# powersupplyboardinprogress.net
KiCad netlist of a schematic drawn in EAGLE
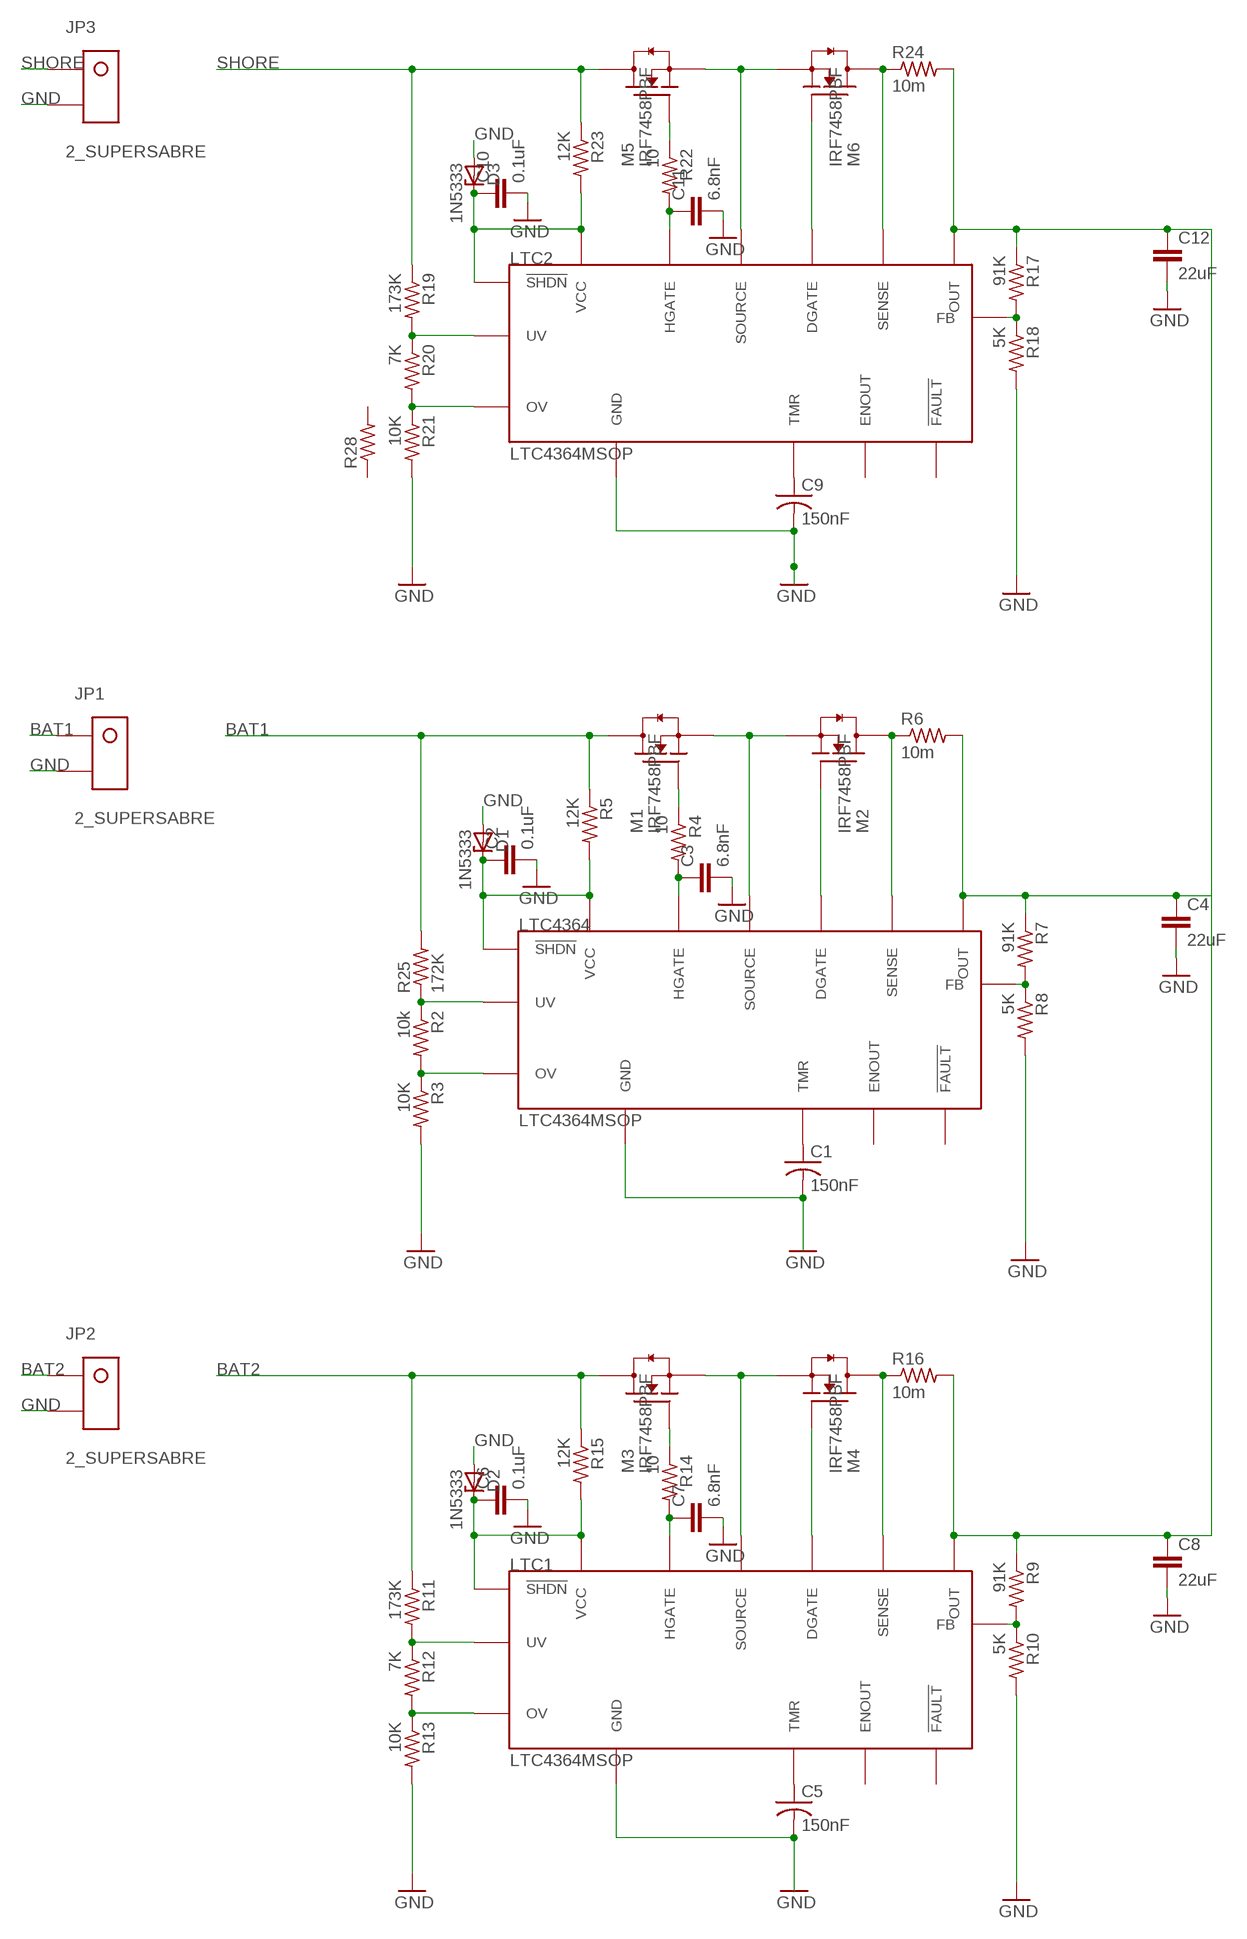
[diagram p0: schematic, sheet 1]

(export (version "E")
  (design (tool "Eeschema 10.0.6"))
  (components
    (comp (ref "C1")
      (value "150nF")
      (footprint "eagle-import:C0805")
      (fields (field (name "SPICEPREFIX") "C"))
      (libsource (lib "eagle-import") (part "C-USC0805"))
    )
    (comp (ref "C2")
      (value "0.1uF")
      (footprint "eagle-import:C0805")
      (libsource (lib "eagle-import") (part "C-EUC0805"))
    )
    (comp (ref "C3")
      (value "6.8nF")
      (footprint "eagle-import:C0805")
      (libsource (lib "eagle-import") (part "C-EUC0805"))
    )
    (comp (ref "C4")
      (value "22uF")
      (footprint "eagle-import:C0805")
      (libsource (lib "eagle-import") (part "C-EUC0805"))
    )
    (comp (ref "C5")
      (value "150nF")
      (footprint "eagle-import:C0805")
      (fields (field (name "SPICEPREFIX") "C"))
      (libsource (lib "eagle-import") (part "C-USC0805"))
    )
    (comp (ref "C6")
      (value "0.1uF")
      (footprint "eagle-import:C0805")
      (libsource (lib "eagle-import") (part "C-EUC0805"))
    )
    (comp (ref "C7")
      (value "6.8nF")
      (footprint "eagle-import:C0805")
      (libsource (lib "eagle-import") (part "C-EUC0805"))
    )
    (comp (ref "C8")
      (value "22uF")
      (footprint "eagle-import:C0805")
      (libsource (lib "eagle-import") (part "C-EUC0805"))
    )
    (comp (ref "C9")
      (value "150nF")
      (footprint "eagle-import:C0805")
      (fields (field (name "SPICEPREFIX") "C"))
      (libsource (lib "eagle-import") (part "C-USC0805"))
    )
    (comp (ref "C10")
      (value "0.1uF")
      (footprint "eagle-import:C0805")
      (libsource (lib "eagle-import") (part "C-EUC0805"))
    )
    (comp (ref "C11")
      (value "6.8nF")
      (footprint "eagle-import:C0805")
      (libsource (lib "eagle-import") (part "C-EUC0805"))
    )
    (comp (ref "C12")
      (value "22uF")
      (footprint "eagle-import:C0805")
      (libsource (lib "eagle-import") (part "C-EUC0805"))
    )
    (comp (ref "D1")
      (value "1N5333")
      (footprint "eagle-import:C1702-15")
      (libsource (lib "eagle-import") (part "1N5333"))
    )
    (comp (ref "D2")
      (value "1N5333")
      (footprint "eagle-import:C1702-15")
      (libsource (lib "eagle-import") (part "1N5333"))
    )
    (comp (ref "D3")
      (value "1N5333")
      (footprint "eagle-import:C1702-15")
      (libsource (lib "eagle-import") (part "1N5333"))
    )
    (comp (ref "JP1")
      (value "2_SUPERSABRE")
      (footprint "eagle-import:SUPERSABRE_2CIRCUIT")
      (libsource (lib "eagle-import") (part "2_SUPERSABRE"))
    )
    (comp (ref "JP2")
      (value "2_SUPERSABRE")
      (footprint "eagle-import:SUPERSABRE_2CIRCUIT")
      (libsource (lib "eagle-import") (part "2_SUPERSABRE"))
    )
    (comp (ref "JP3")
      (value "2_SUPERSABRE")
      (footprint "eagle-import:SUPERSABRE_2CIRCUIT")
      (libsource (lib "eagle-import") (part "2_SUPERSABRE"))
    )
    (comp (ref "LTC1")
      (value "LTC4364MSOP")
      (footprint "eagle-import:MSOP16")
      (fields (field (name "SPICEPREFIX") "X"))
      (libsource (lib "eagle-import") (part "LTC4364MSOP"))
    )
    (comp (ref "LTC2")
      (value "LTC4364MSOP")
      (footprint "eagle-import:MSOP16")
      (fields (field (name "SPICEPREFIX") "X"))
      (libsource (lib "eagle-import") (part "LTC4364MSOP"))
    )
    (comp (ref "LTC4364")
      (value "LTC4364MSOP")
      (footprint "eagle-import:MSOP16")
      (fields (field (name "SPICEPREFIX") "X"))
      (libsource (lib "eagle-import") (part "LTC4364MSOP"))
    )
    (comp (ref "M1")
      (value "IRF7458PBF")
      (footprint "eagle-import:SOIC8")
      (fields (field (name "SPICEPREFIX") "M"))
      (libsource (lib "eagle-import") (part "IRF7458PBF"))
    )
    (comp (ref "M2")
      (value "IRF7458PBF")
      (footprint "eagle-import:SOIC8")
      (fields (field (name "SPICEPREFIX") "M"))
      (libsource (lib "eagle-import") (part "IRF7458PBF"))
    )
    (comp (ref "M3")
      (value "IRF7458PBF")
      (footprint "eagle-import:SOIC8")
      (fields (field (name "SPICEPREFIX") "M"))
      (libsource (lib "eagle-import") (part "IRF7458PBF"))
    )
    (comp (ref "M4")
      (value "IRF7458PBF")
      (footprint "eagle-import:SOIC8")
      (fields (field (name "SPICEPREFIX") "M"))
      (libsource (lib "eagle-import") (part "IRF7458PBF"))
    )
    (comp (ref "M5")
      (value "IRF7458PBF")
      (footprint "eagle-import:SOIC8")
      (fields (field (name "SPICEPREFIX") "M"))
      (libsource (lib "eagle-import") (part "IRF7458PBF"))
    )
    (comp (ref "M6")
      (value "IRF7458PBF")
      (footprint "eagle-import:SOIC8")
      (fields (field (name "SPICEPREFIX") "M"))
      (libsource (lib "eagle-import") (part "IRF7458PBF"))
    )
    (comp (ref "R2")
      (value "10k")
      (footprint "eagle-import:R0805")
      (libsource (lib "eagle-import") (part "R-US_R0805"))
    )
    (comp (ref "R3")
      (value "10K")
      (footprint "eagle-import:R0805")
      (libsource (lib "eagle-import") (part "R-US_R0805"))
    )
    (comp (ref "R4")
      (value "10")
      (footprint "eagle-import:R0805")
      (libsource (lib "eagle-import") (part "R-US_R0805"))
    )
    (comp (ref "R5")
      (value "12K")
      (footprint "eagle-import:R0805")
      (libsource (lib "eagle-import") (part "R-US_R0805"))
    )
    (comp (ref "R6")
      (value "10m")
      (footprint "eagle-import:R0805")
      (libsource (lib "eagle-import") (part "R-US_R0805"))
    )
    (comp (ref "R7")
      (value "91K")
      (footprint "eagle-import:R0805")
      (libsource (lib "eagle-import") (part "R-US_R0805"))
    )
    (comp (ref "R8")
      (value "5K")
      (footprint "eagle-import:R0805")
      (libsource (lib "eagle-import") (part "R-US_R0805"))
    )
    (comp (ref "R9")
      (value "91K")
      (footprint "eagle-import:R0805")
      (libsource (lib "eagle-import") (part "R-US_R0805"))
    )
    (comp (ref "R10")
      (value "5K")
      (footprint "eagle-import:R0805")
      (libsource (lib "eagle-import") (part "R-US_R0805"))
    )
    (comp (ref "R11")
      (value "173K")
      (footprint "eagle-import:R0805")
      (libsource (lib "eagle-import") (part "R-US_R0805"))
    )
    (comp (ref "R12")
      (value "7K")
      (footprint "eagle-import:R0805")
      (libsource (lib "eagle-import") (part "R-US_R0805"))
    )
    (comp (ref "R13")
      (value "10K")
      (footprint "eagle-import:R0805")
      (libsource (lib "eagle-import") (part "R-US_R0805"))
    )
    (comp (ref "R14")
      (value "10")
      (footprint "eagle-import:R0805")
      (libsource (lib "eagle-import") (part "R-US_R0805"))
    )
    (comp (ref "R15")
      (value "12K")
      (footprint "eagle-import:R0805")
      (libsource (lib "eagle-import") (part "R-US_R0805"))
    )
    (comp (ref "R16")
      (value "10m")
      (footprint "eagle-import:R0805")
      (libsource (lib "eagle-import") (part "R-US_R0805"))
    )
    (comp (ref "R17")
      (value "91K")
      (footprint "eagle-import:R0805")
      (libsource (lib "eagle-import") (part "R-US_R0805"))
    )
    (comp (ref "R18")
      (value "5K")
      (footprint "eagle-import:R0805")
      (libsource (lib "eagle-import") (part "R-US_R0805"))
    )
    (comp (ref "R19")
      (value "173K")
      (footprint "eagle-import:R0805")
      (libsource (lib "eagle-import") (part "R-US_R0805"))
    )
    (comp (ref "R20")
      (value "7K")
      (footprint "eagle-import:R0805")
      (libsource (lib "eagle-import") (part "R-US_R0805"))
    )
    (comp (ref "R21")
      (value "10K")
      (footprint "eagle-import:R0805")
      (libsource (lib "eagle-import") (part "R-US_R0805"))
    )
    (comp (ref "R22")
      (value "10")
      (footprint "eagle-import:R0805")
      (libsource (lib "eagle-import") (part "R-US_R0805"))
    )
    (comp (ref "R23")
      (value "12K")
      (footprint "eagle-import:R0805")
      (libsource (lib "eagle-import") (part "R-US_R0805"))
    )
    (comp (ref "R24")
      (value "10m")
      (footprint "eagle-import:R0805")
      (libsource (lib "eagle-import") (part "R-US_R0805"))
    )
    (comp (ref "R25")
      (value "172K")
      (footprint "eagle-import:R0603")
      (libsource (lib "eagle-import") (part "R-US_R0603"))
    )
    (comp (ref "R28")
      (value "R-US_R0603")
      (footprint "eagle-import:R0603")
      (libsource (lib "eagle-import") (part "R-US_R0603"))
    )
  )
  (nets
    (net (code "1") (name "/BAT1") (class "Default")
      (node (ref "JP1") (pin "P$1") (pinfunction "P$1_P$1") (pintype "bidirectional"))
      (node (ref "M1") (pin "D1") (pinfunction "D_D1") (pintype "bidirectional"))
      (node (ref "M1") (pin "D2") (pinfunction "D_D2") (pintype "bidirectional"))
      (node (ref "M1") (pin "D3") (pinfunction "D_D3") (pintype "bidirectional"))
      (node (ref "M1") (pin "D4") (pinfunction "D_D4") (pintype "bidirectional"))
      (node (ref "R25") (pin "2") (pinfunction "2_2") (pintype "passive"))
      (node (ref "R5") (pin "1") (pinfunction "1_1") (pintype "passive"))
    )
    (net (code "2") (name "/BAT2") (class "Default")
      (node (ref "JP2") (pin "P$1") (pinfunction "P$1_P$1") (pintype "bidirectional"))
      (node (ref "M3") (pin "D1") (pinfunction "D_D1") (pintype "bidirectional"))
      (node (ref "M3") (pin "D2") (pinfunction "D_D2") (pintype "bidirectional"))
      (node (ref "M3") (pin "D3") (pinfunction "D_D3") (pintype "bidirectional"))
      (node (ref "M3") (pin "D4") (pinfunction "D_D4") (pintype "bidirectional"))
      (node (ref "R11") (pin "1") (pinfunction "1_1") (pintype "passive"))
      (node (ref "R15") (pin "1") (pinfunction "1_1") (pintype "passive"))
    )
    (net (code "3") (name "/SHORE") (class "Default")
      (node (ref "JP3") (pin "P$1") (pinfunction "P$1_P$1") (pintype "bidirectional"))
      (node (ref "M5") (pin "D1") (pinfunction "D_D1") (pintype "bidirectional"))
      (node (ref "M5") (pin "D2") (pinfunction "D_D2") (pintype "bidirectional"))
      (node (ref "M5") (pin "D3") (pinfunction "D_D3") (pintype "bidirectional"))
      (node (ref "M5") (pin "D4") (pinfunction "D_D4") (pintype "bidirectional"))
      (node (ref "R19") (pin "1") (pinfunction "1_1") (pintype "passive"))
      (node (ref "R23") (pin "1") (pinfunction "1_1") (pintype "passive"))
    )
    (net (code "4") (name "GND") (class "Default")
      (node (ref "C1") (pin "2") (pinfunction "2_2") (pintype "passive"))
      (node (ref "C10") (pin "2") (pinfunction "2_2") (pintype "passive"))
      (node (ref "C11") (pin "2") (pinfunction "2_2") (pintype "passive"))
      (node (ref "C12") (pin "2") (pinfunction "2_2") (pintype "passive"))
      (node (ref "C2") (pin "2") (pinfunction "2_2") (pintype "passive"))
      (node (ref "C3") (pin "2") (pinfunction "2_2") (pintype "passive"))
      (node (ref "C4") (pin "2") (pinfunction "2_2") (pintype "passive"))
      (node (ref "C5") (pin "2") (pinfunction "2_2") (pintype "passive"))
      (node (ref "C6") (pin "2") (pinfunction "2_2") (pintype "passive"))
      (node (ref "C7") (pin "2") (pinfunction "2_2") (pintype "passive"))
      (node (ref "C8") (pin "2") (pinfunction "2_2") (pintype "passive"))
      (node (ref "C9") (pin "2") (pinfunction "2_2") (pintype "passive"))
      (node (ref "D1") (pin "A") (pinfunction "A_A") (pintype "passive"))
      (node (ref "D2") (pin "A") (pinfunction "A_A") (pintype "passive"))
      (node (ref "D3") (pin "A") (pinfunction "A_A") (pintype "passive"))
      (node (ref "JP1") (pin "P$2") (pinfunction "P$2_P$2") (pintype "bidirectional"))
      (node (ref "JP2") (pin "P$2") (pinfunction "P$2_P$2") (pintype "bidirectional"))
      (node (ref "JP3") (pin "P$2") (pinfunction "P$2_P$2") (pintype "bidirectional"))
      (node (ref "LTC1") (pin "GND") (pinfunction "GND_GND") (pintype "bidirectional"))
      (node (ref "LTC2") (pin "GND") (pinfunction "GND_GND") (pintype "bidirectional"))
      (node (ref "LTC4364") (pin "GND") (pinfunction "GND_GND") (pintype "bidirectional"))
      (node (ref "R10") (pin "2") (pinfunction "2_2") (pintype "passive"))
      (node (ref "R13") (pin "2") (pinfunction "2_2") (pintype "passive"))
      (node (ref "R18") (pin "2") (pinfunction "2_2") (pintype "passive"))
      (node (ref "R21") (pin "2") (pinfunction "2_2") (pintype "passive"))
      (node (ref "R3") (pin "2") (pinfunction "2_2") (pintype "passive"))
      (node (ref "R8") (pin "2") (pinfunction "2_2") (pintype "passive"))
    )
    (net (code "5") (name "Net-(C1-Pad1)") (class "Default")
      (node (ref "C1") (pin "1") (pinfunction "1_1") (pintype "passive"))
      (node (ref "LTC4364") (pin "TMR") (pinfunction "TMR_TMR") (pintype "bidirectional"))
    )
    (net (code "6") (name "Net-(C3-Pad1)") (class "Default")
      (node (ref "C3") (pin "1") (pinfunction "1_1") (pintype "passive"))
      (node (ref "LTC4364") (pin "HGATE") (pinfunction "HGATE_HGATE") (pintype "bidirectional"))
      (node (ref "R4") (pin "2") (pinfunction "2_2") (pintype "passive"))
    )
    (net (code "7") (name "Net-(C5-Pad1)") (class "Default")
      (node (ref "C5") (pin "1") (pinfunction "1_1") (pintype "passive"))
      (node (ref "LTC1") (pin "TMR") (pinfunction "TMR_TMR") (pintype "bidirectional"))
    )
    (net (code "8") (name "Net-(C7-Pad1)") (class "Default")
      (node (ref "C7") (pin "1") (pinfunction "1_1") (pintype "passive"))
      (node (ref "LTC1") (pin "HGATE") (pinfunction "HGATE_HGATE") (pintype "bidirectional"))
      (node (ref "R14") (pin "2") (pinfunction "2_2") (pintype "passive"))
    )
    (net (code "9") (name "Net-(C9-Pad1)") (class "Default")
      (node (ref "C9") (pin "1") (pinfunction "1_1") (pintype "passive"))
      (node (ref "LTC2") (pin "TMR") (pinfunction "TMR_TMR") (pintype "bidirectional"))
    )
    (net (code "10") (name "Net-(C11-Pad1)") (class "Default")
      (node (ref "C11") (pin "1") (pinfunction "1_1") (pintype "passive"))
      (node (ref "LTC2") (pin "HGATE") (pinfunction "HGATE_HGATE") (pintype "bidirectional"))
      (node (ref "R22") (pin "2") (pinfunction "2_2") (pintype "passive"))
    )
    (net (code "11") (name "Net-(C12-Pad1)") (class "Default")
      (node (ref "C12") (pin "1") (pinfunction "1_1") (pintype "passive"))
      (node (ref "C4") (pin "1") (pinfunction "1_1") (pintype "passive"))
      (node (ref "C8") (pin "1") (pinfunction "1_1") (pintype "passive"))
      (node (ref "LTC1") (pin "OUT") (pinfunction "OUT_OUT") (pintype "bidirectional"))
      (node (ref "LTC2") (pin "OUT") (pinfunction "OUT_OUT") (pintype "bidirectional"))
      (node (ref "LTC4364") (pin "OUT") (pinfunction "OUT_OUT") (pintype "bidirectional"))
      (node (ref "R16") (pin "2") (pinfunction "2_2") (pintype "passive"))
      (node (ref "R17") (pin "1") (pinfunction "1_1") (pintype "passive"))
      (node (ref "R24") (pin "2") (pinfunction "2_2") (pintype "passive"))
      (node (ref "R6") (pin "2") (pinfunction "2_2") (pintype "passive"))
      (node (ref "R7") (pin "1") (pinfunction "1_1") (pintype "passive"))
      (node (ref "R9") (pin "1") (pinfunction "1_1") (pintype "passive"))
    )
    (net (code "12") (name "Net-(LTC1-PadFB)") (class "Default")
      (node (ref "LTC1") (pin "FB") (pinfunction "FB_FB") (pintype "bidirectional"))
      (node (ref "R10") (pin "1") (pinfunction "1_1") (pintype "passive"))
      (node (ref "R9") (pin "2") (pinfunction "2_2") (pintype "passive"))
    )
    (net (code "13") (name "Net-(LTC1-PadOV)") (class "Default")
      (node (ref "LTC1") (pin "OV") (pinfunction "OV_OV") (pintype "bidirectional"))
      (node (ref "R12") (pin "2") (pinfunction "2_2") (pintype "passive"))
      (node (ref "R13") (pin "1") (pinfunction "1_1") (pintype "passive"))
    )
    (net (code "14") (name "Net-(LTC1-PadSENSE)") (class "Default")
      (node (ref "LTC1") (pin "SENSE") (pinfunction "SENSE_SENSE") (pintype "bidirectional"))
      (node (ref "M4") (pin "D1") (pinfunction "D_D1") (pintype "bidirectional"))
      (node (ref "M4") (pin "D2") (pinfunction "D_D2") (pintype "bidirectional"))
      (node (ref "M4") (pin "D3") (pinfunction "D_D3") (pintype "bidirectional"))
      (node (ref "M4") (pin "D4") (pinfunction "D_D4") (pintype "bidirectional"))
      (node (ref "R16") (pin "1") (pinfunction "1_1") (pintype "passive"))
    )
    (net (code "15") (name "Net-(LTC1-PadSOURCE)") (class "Default")
      (node (ref "LTC1") (pin "SOURCE") (pinfunction "SOURCE_SOURCE") (pintype "bidirectional"))
      (node (ref "M3") (pin "S1") (pinfunction "S_S1") (pintype "passive"))
      (node (ref "M3") (pin "S2") (pinfunction "S_S2") (pintype "passive"))
      (node (ref "M3") (pin "S3") (pinfunction "S_S3") (pintype "passive"))
      (node (ref "M4") (pin "S1") (pinfunction "S_S1") (pintype "passive"))
      (node (ref "M4") (pin "S2") (pinfunction "S_S2") (pintype "passive"))
      (node (ref "M4") (pin "S3") (pinfunction "S_S3") (pintype "passive"))
    )
    (net (code "16") (name "Net-(LTC1-PadUV)") (class "Default")
      (node (ref "LTC1") (pin "UV") (pinfunction "UV_UV") (pintype "bidirectional"))
      (node (ref "R11") (pin "2") (pinfunction "2_2") (pintype "passive"))
      (node (ref "R12") (pin "1") (pinfunction "1_1") (pintype "passive"))
    )
    (net (code "17") (name "Net-(LTC1-~{SHDN})") (class "Default")
      (node (ref "C6") (pin "1") (pinfunction "1_1") (pintype "passive"))
      (node (ref "D2") (pin "C") (pinfunction "C_C") (pintype "passive"))
      (node (ref "LTC1") (pin "SHDN") (pinfunction "~{SHDN}_SHDN") (pintype "bidirectional"))
      (node (ref "LTC1") (pin "VCC") (pinfunction "VCC_VCC") (pintype "bidirectional"))
      (node (ref "R15") (pin "2") (pinfunction "2_2") (pintype "passive"))
    )
    (net (code "18") (name "Net-(LTC2-PadFB)") (class "Default")
      (node (ref "LTC2") (pin "FB") (pinfunction "FB_FB") (pintype "bidirectional"))
      (node (ref "R17") (pin "2") (pinfunction "2_2") (pintype "passive"))
      (node (ref "R18") (pin "1") (pinfunction "1_1") (pintype "passive"))
    )
    (net (code "19") (name "Net-(LTC2-PadOV)") (class "Default")
      (node (ref "LTC2") (pin "OV") (pinfunction "OV_OV") (pintype "bidirectional"))
      (node (ref "R20") (pin "2") (pinfunction "2_2") (pintype "passive"))
      (node (ref "R21") (pin "1") (pinfunction "1_1") (pintype "passive"))
    )
    (net (code "20") (name "Net-(LTC2-PadSENSE)") (class "Default")
      (node (ref "LTC2") (pin "SENSE") (pinfunction "SENSE_SENSE") (pintype "bidirectional"))
      (node (ref "M6") (pin "D1") (pinfunction "D_D1") (pintype "bidirectional"))
      (node (ref "M6") (pin "D2") (pinfunction "D_D2") (pintype "bidirectional"))
      (node (ref "M6") (pin "D3") (pinfunction "D_D3") (pintype "bidirectional"))
      (node (ref "M6") (pin "D4") (pinfunction "D_D4") (pintype "bidirectional"))
      (node (ref "R24") (pin "1") (pinfunction "1_1") (pintype "passive"))
    )
    (net (code "21") (name "Net-(LTC2-PadSOURCE)") (class "Default")
      (node (ref "LTC2") (pin "SOURCE") (pinfunction "SOURCE_SOURCE") (pintype "bidirectional"))
      (node (ref "M5") (pin "S1") (pinfunction "S_S1") (pintype "passive"))
      (node (ref "M5") (pin "S2") (pinfunction "S_S2") (pintype "passive"))
      (node (ref "M5") (pin "S3") (pinfunction "S_S3") (pintype "passive"))
      (node (ref "M6") (pin "S1") (pinfunction "S_S1") (pintype "passive"))
      (node (ref "M6") (pin "S2") (pinfunction "S_S2") (pintype "passive"))
      (node (ref "M6") (pin "S3") (pinfunction "S_S3") (pintype "passive"))
    )
    (net (code "22") (name "Net-(LTC2-PadUV)") (class "Default")
      (node (ref "LTC2") (pin "UV") (pinfunction "UV_UV") (pintype "bidirectional"))
      (node (ref "R19") (pin "2") (pinfunction "2_2") (pintype "passive"))
      (node (ref "R20") (pin "1") (pinfunction "1_1") (pintype "passive"))
    )
    (net (code "23") (name "Net-(LTC2-~{SHDN})") (class "Default")
      (node (ref "C10") (pin "1") (pinfunction "1_1") (pintype "passive"))
      (node (ref "D3") (pin "C") (pinfunction "C_C") (pintype "passive"))
      (node (ref "LTC2") (pin "SHDN") (pinfunction "~{SHDN}_SHDN") (pintype "bidirectional"))
      (node (ref "LTC2") (pin "VCC") (pinfunction "VCC_VCC") (pintype "bidirectional"))
      (node (ref "R23") (pin "2") (pinfunction "2_2") (pintype "passive"))
    )
    (net (code "24") (name "Net-(LTC4364-PadFB)") (class "Default")
      (node (ref "LTC4364") (pin "FB") (pinfunction "FB_FB") (pintype "bidirectional"))
      (node (ref "R7") (pin "2") (pinfunction "2_2") (pintype "passive"))
      (node (ref "R8") (pin "1") (pinfunction "1_1") (pintype "passive"))
    )
    (net (code "25") (name "Net-(LTC4364-PadOV)") (class "Default")
      (node (ref "LTC4364") (pin "OV") (pinfunction "OV_OV") (pintype "bidirectional"))
      (node (ref "R2") (pin "2") (pinfunction "2_2") (pintype "passive"))
      (node (ref "R3") (pin "1") (pinfunction "1_1") (pintype "passive"))
    )
    (net (code "26") (name "Net-(LTC4364-PadSENSE)") (class "Default")
      (node (ref "LTC4364") (pin "SENSE") (pinfunction "SENSE_SENSE") (pintype "bidirectional"))
      (node (ref "M2") (pin "D1") (pinfunction "D_D1") (pintype "bidirectional"))
      (node (ref "M2") (pin "D2") (pinfunction "D_D2") (pintype "bidirectional"))
      (node (ref "M2") (pin "D3") (pinfunction "D_D3") (pintype "bidirectional"))
      (node (ref "M2") (pin "D4") (pinfunction "D_D4") (pintype "bidirectional"))
      (node (ref "R6") (pin "1") (pinfunction "1_1") (pintype "passive"))
    )
    (net (code "27") (name "Net-(LTC4364-PadSOURCE)") (class "Default")
      (node (ref "LTC4364") (pin "SOURCE") (pinfunction "SOURCE_SOURCE") (pintype "bidirectional"))
      (node (ref "M1") (pin "S1") (pinfunction "S_S1") (pintype "passive"))
      (node (ref "M1") (pin "S2") (pinfunction "S_S2") (pintype "passive"))
      (node (ref "M1") (pin "S3") (pinfunction "S_S3") (pintype "passive"))
      (node (ref "M2") (pin "S1") (pinfunction "S_S1") (pintype "passive"))
      (node (ref "M2") (pin "S2") (pinfunction "S_S2") (pintype "passive"))
      (node (ref "M2") (pin "S3") (pinfunction "S_S3") (pintype "passive"))
    )
    (net (code "28") (name "Net-(LTC4364-PadUV)") (class "Default")
      (node (ref "LTC4364") (pin "UV") (pinfunction "UV_UV") (pintype "bidirectional"))
      (node (ref "R2") (pin "1") (pinfunction "1_1") (pintype "passive"))
      (node (ref "R25") (pin "1") (pinfunction "1_1") (pintype "passive"))
    )
    (net (code "29") (name "Net-(LTC4364-~{SHDN})") (class "Default")
      (node (ref "C2") (pin "1") (pinfunction "1_1") (pintype "passive"))
      (node (ref "D1") (pin "C") (pinfunction "C_C") (pintype "passive"))
      (node (ref "LTC4364") (pin "SHDN") (pinfunction "~{SHDN}_SHDN") (pintype "bidirectional"))
      (node (ref "LTC4364") (pin "VCC") (pinfunction "VCC_VCC") (pintype "bidirectional"))
      (node (ref "R5") (pin "2") (pinfunction "2_2") (pintype "passive"))
    )
    (net (code "30") (name "Net-(M1-G)") (class "Default")
      (node (ref "M1") (pin "G1") (pinfunction "G_G1") (pintype "passive"))
      (node (ref "R4") (pin "1") (pinfunction "1_1") (pintype "passive"))
    )
    (net (code "31") (name "Net-(M2-G)") (class "Default")
      (node (ref "LTC4364") (pin "DGATE") (pinfunction "DGATE_DGATE") (pintype "bidirectional"))
      (node (ref "M2") (pin "G1") (pinfunction "G_G1") (pintype "passive"))
    )
    (net (code "32") (name "Net-(M3-G)") (class "Default")
      (node (ref "M3") (pin "G1") (pinfunction "G_G1") (pintype "passive"))
      (node (ref "R14") (pin "1") (pinfunction "1_1") (pintype "passive"))
    )
    (net (code "33") (name "Net-(M4-G)") (class "Default")
      (node (ref "LTC1") (pin "DGATE") (pinfunction "DGATE_DGATE") (pintype "bidirectional"))
      (node (ref "M4") (pin "G1") (pinfunction "G_G1") (pintype "passive"))
    )
    (net (code "34") (name "Net-(M5-G)") (class "Default")
      (node (ref "M5") (pin "G1") (pinfunction "G_G1") (pintype "passive"))
      (node (ref "R22") (pin "1") (pinfunction "1_1") (pintype "passive"))
    )
    (net (code "35") (name "Net-(M6-G)") (class "Default")
      (node (ref "LTC2") (pin "DGATE") (pinfunction "DGATE_DGATE") (pintype "bidirectional"))
      (node (ref "M6") (pin "G1") (pinfunction "G_G1") (pintype "passive"))
    )
    (net (code "36") (name "unconnected-(LTC1-PadENOUT)") (class "Default")
      (node (ref "LTC1") (pin "ENOUT") (pinfunction "ENOUT_ENOUT") (pintype "bidirectional"))
    )
    (net (code "37") (name "unconnected-(LTC1-~{FAULT}-PadFLT)") (class "Default")
      (node (ref "LTC1") (pin "FLT") (pinfunction "~{FAULT}_FLT") (pintype "bidirectional"))
    )
    (net (code "38") (name "unconnected-(LTC2-PadENOUT)") (class "Default")
      (node (ref "LTC2") (pin "ENOUT") (pinfunction "ENOUT_ENOUT") (pintype "bidirectional"))
    )
    (net (code "39") (name "unconnected-(LTC2-~{FAULT}-PadFLT)") (class "Default")
      (node (ref "LTC2") (pin "FLT") (pinfunction "~{FAULT}_FLT") (pintype "bidirectional"))
    )
    (net (code "40") (name "unconnected-(LTC4364-PadENOUT)") (class "Default")
      (node (ref "LTC4364") (pin "ENOUT") (pinfunction "ENOUT_ENOUT") (pintype "bidirectional"))
    )
    (net (code "41") (name "unconnected-(LTC4364-~{FAULT}-PadFLT)") (class "Default")
      (node (ref "LTC4364") (pin "FLT") (pinfunction "~{FAULT}_FLT") (pintype "bidirectional"))
    )
    (net (code "42") (name "unconnected-(R28-Pad1)") (class "Default")
      (node (ref "R28") (pin "1") (pinfunction "1_1") (pintype "passive"))
    )
    (net (code "43") (name "unconnected-(R28-Pad2)") (class "Default")
      (node (ref "R28") (pin "2") (pinfunction "2_2") (pintype "passive"))
    )
  )
)
